# 12-FPGA_Power.net
KiCad netlist of a schematic drawn in Altium Designer
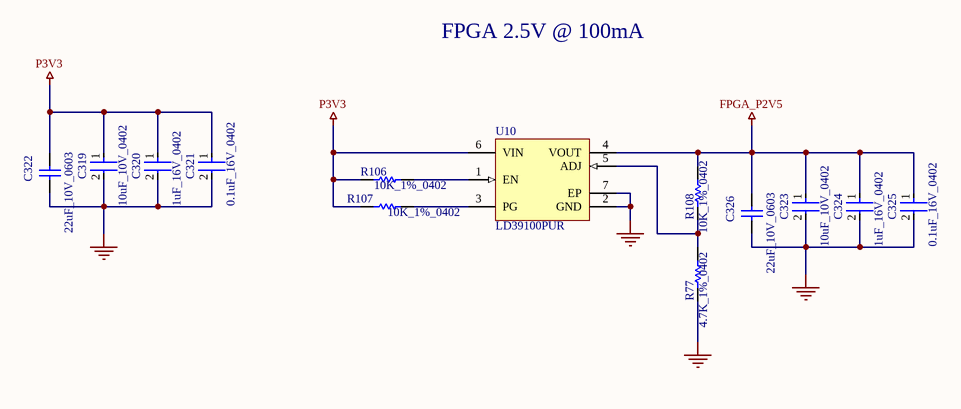
[diagram p0: 12-FPGA_Power.SchDoc]

(export (version "E")
  (design (tool "Eeschema 10.0.6"))
  (components
    (comp (ref "C319")
      (value "10uF_10V_0402")
      (footprint "FP-CL05A106MP5NUNC-MFG")
      (description "CAP CER 10UF 10V X5R 0402")
      (fields
        (field (name "OCTOPART") "https://octopart.com/cl05a106mp5nunc-samsung-22457395")
        (field (name "TOLERANCE") "20%")
      )
      (libsource (lib "Altium Content Vault") (part "b4654b650e69147ec39a6b967a45e02"))
    )
    (comp (ref "C320")
      (value "1uF_16V_0402")
      (footprint "FP-0402-L_1_0_0_05-W_0_5-IPC_A")
      (description "None")
      (fields (field (name "TOLERANCE") "10%"))
      (libsource (lib "Altium Content Vault") (part "b4654b650e69147ec39a6b967a45e02"))
    )
    (comp (ref "C321")
      (value "0.1uF_16V_0402")
      (footprint "FP-C0402-BB-MFG")
      (description "CAP CER 0.1UF 16V 5% X7R 0402")
      (fields
        (field (name "MANUFACTURER") "Kemet")
        (field (name "MANUFACTURER PART NUMBER") "C0402C104J4RACTU")
      )
      (libsource (lib "Altium Content Vault") (part "b4654b650e69147ec39a6b967a45e02"))
    )
    (comp (ref "C322")
      (value "22uF_10V_0603")
      (footprint "CAPC1608X100X20ML10")
      (description "Chip Capacitor, 22 uF, +/- 20%, 10 V, -55 to 85 degC, 0603 (1608 Metric), RoHS, Tape and Reel")
      (fields (field (name "MANUFACTURER") "TDK") (field (name "TOLERANCE") "±20%"))
      (libsource (lib "Altium Content Vault") (part "CAP-NP-2"))
    )
    (comp (ref "C323")
      (value "10uF_10V_0402")
      (footprint "FP-CL05A106MP5NUNC-MFG")
      (description "CAP CER 10UF 10V X5R 0402")
      (fields
        (field (name "OCTOPART") "https://octopart.com/cl05a106mp5nunc-samsung-22457395")
        (field (name "TOLERANCE") "20%")
      )
      (libsource (lib "Altium Content Vault") (part "b4654b650e69147ec39a6b967a45e02"))
    )
    (comp (ref "C324")
      (value "1uF_16V_0402")
      (footprint "FP-0402-L_1_0_0_05-W_0_5-IPC_A")
      (description "None")
      (fields (field (name "TOLERANCE") "10%"))
      (libsource (lib "Altium Content Vault") (part "b4654b650e69147ec39a6b967a45e02"))
    )
    (comp (ref "C325")
      (value "0.1uF_16V_0402")
      (footprint "FP-C0402-BB-MFG")
      (description "CAP CER 0.1UF 16V 5% X7R 0402")
      (fields
        (field (name "MANUFACTURER") "Kemet")
        (field (name "MANUFACTURER PART NUMBER") "C0402C104J4RACTU")
      )
      (libsource (lib "Altium Content Vault") (part "b4654b650e69147ec39a6b967a45e02"))
    )
    (comp (ref "C326")
      (value "22uF_10V_0603")
      (footprint "CAPC1608X100X20ML10")
      (description "Chip Capacitor, 22 uF, +/- 20%, 10 V, -55 to 85 degC, 0603 (1608 Metric), RoHS, Tape and Reel")
      (fields (field (name "MANUFACTURER") "TDK") (field (name "TOLERANCE") "±20%"))
      (libsource (lib "Altium Content Vault") (part "CAP-NP-2"))
    )
    (comp (ref "R77")
      (value "4.7K_1%_0402")
      (footprint "RESC1005X40X25NL10T10")
      (fields (field (name "MANUFACTURER") "Bourns") (field (name "PART NUMBER") "CR0402-FX-4701GLF"))
      (libsource (lib "Altium Content Vault") (part "RES"))
    )
    (comp (ref "R106")
      (value "10K_1%_0402")
      (footprint "RESC1005X40X25NL10T10")
      (fields (field (name "MANUFACTURER") "Bourns") (field (name "PART NUMBER") "CR0402-FX-1002GLF"))
      (libsource (lib "Altium Content Vault") (part "RES"))
    )
    (comp (ref "R107")
      (value "10K_1%_0402")
      (footprint "RESC1005X40X25NL10T10")
      (fields (field (name "MANUFACTURER") "Bourns") (field (name "PART NUMBER") "CR0402-FX-1002GLF"))
      (libsource (lib "Altium Content Vault") (part "RES"))
    )
    (comp (ref "R108")
      (value "10K_1%_0402")
      (footprint "RESC1005X40X25NL10T10")
      (fields (field (name "MANUFACTURER") "Bourns") (field (name "PART NUMBER") "CR0402-FX-1002GLF"))
      (libsource (lib "Altium Content Vault") (part "RES"))
    )
    (comp (ref "U10")
      (value "LD39100PUR")
      (footprint "DFN6D_M")
      (libsource (lib "Altium Content Vault") (part "PM-REG-LD39050-SQ7A"))
    )
  )
  (nets
    (net (code "1") (name "FPGA_P2V5") (class "Default")
      (node (ref "C323") (pin "1") (pinfunction "1_1") (pintype "passive"))
      (node (ref "C324") (pin "1") (pinfunction "1_1") (pintype "passive"))
      (node (ref "C325") (pin "1") (pinfunction "1_1") (pintype "passive"))
      (node (ref "C326") (pin "2") (pinfunction "2_2") (pintype "passive"))
      (node (ref "R108") (pin "2") (pinfunction "2_2") (pintype "passive"))
      (node (ref "U10") (pin "4") (pinfunction "VOUT_4") (pintype "power_in"))
    )
    (net (code "2") (name "GND") (class "Default")
      (node (ref "C319") (pin "2") (pinfunction "2_2") (pintype "passive"))
      (node (ref "C320") (pin "2") (pinfunction "2_2") (pintype "passive"))
      (node (ref "C321") (pin "2") (pinfunction "2_2") (pintype "passive"))
      (node (ref "C322") (pin "1") (pinfunction "1_1") (pintype "passive"))
      (node (ref "C323") (pin "2") (pinfunction "2_2") (pintype "passive"))
      (node (ref "C324") (pin "2") (pinfunction "2_2") (pintype "passive"))
      (node (ref "C325") (pin "2") (pinfunction "2_2") (pintype "passive"))
      (node (ref "C326") (pin "1") (pinfunction "1_1") (pintype "passive"))
      (node (ref "R77") (pin "1") (pinfunction "1_1") (pintype "passive"))
      (node (ref "U10") (pin "2") (pinfunction "GND_2") (pintype "power_in"))
      (node (ref "U10") (pin "7") (pinfunction "EP_7") (pintype "power_in"))
    )
    (net (code "3") (name "Net-(U10-ADJ)") (class "Default")
      (node (ref "R108") (pin "1") (pinfunction "1_1") (pintype "passive"))
      (node (ref "R77") (pin "2") (pinfunction "2_2") (pintype "passive"))
      (node (ref "U10") (pin "5") (pinfunction "ADJ_5") (pintype "input"))
    )
    (net (code "4") (name "Net-(U10-EN)") (class "Default")
      (node (ref "R106") (pin "1") (pinfunction "1_1") (pintype "passive"))
      (node (ref "U10") (pin "1") (pinfunction "EN_1") (pintype "input"))
    )
    (net (code "5") (name "Net-(U10-PG)") (class "Default")
      (node (ref "R107") (pin "1") (pinfunction "1_1") (pintype "passive"))
      (node (ref "U10") (pin "3") (pinfunction "PG_3") (pintype "open_collector"))
    )
    (net (code "6") (name "P3V3") (class "Default")
      (node (ref "C319") (pin "1") (pinfunction "1_1") (pintype "passive"))
      (node (ref "C320") (pin "1") (pinfunction "1_1") (pintype "passive"))
      (node (ref "C321") (pin "1") (pinfunction "1_1") (pintype "passive"))
      (node (ref "C322") (pin "2") (pinfunction "2_2") (pintype "passive"))
      (node (ref "R106") (pin "2") (pinfunction "2_2") (pintype "passive"))
      (node (ref "R107") (pin "2") (pinfunction "2_2") (pintype "passive"))
      (node (ref "U10") (pin "6") (pinfunction "VIN_6") (pintype "power_in"))
    )
  )
)
